# SoC.net
KiCad netlist of a schematic drawn in Altium Designer
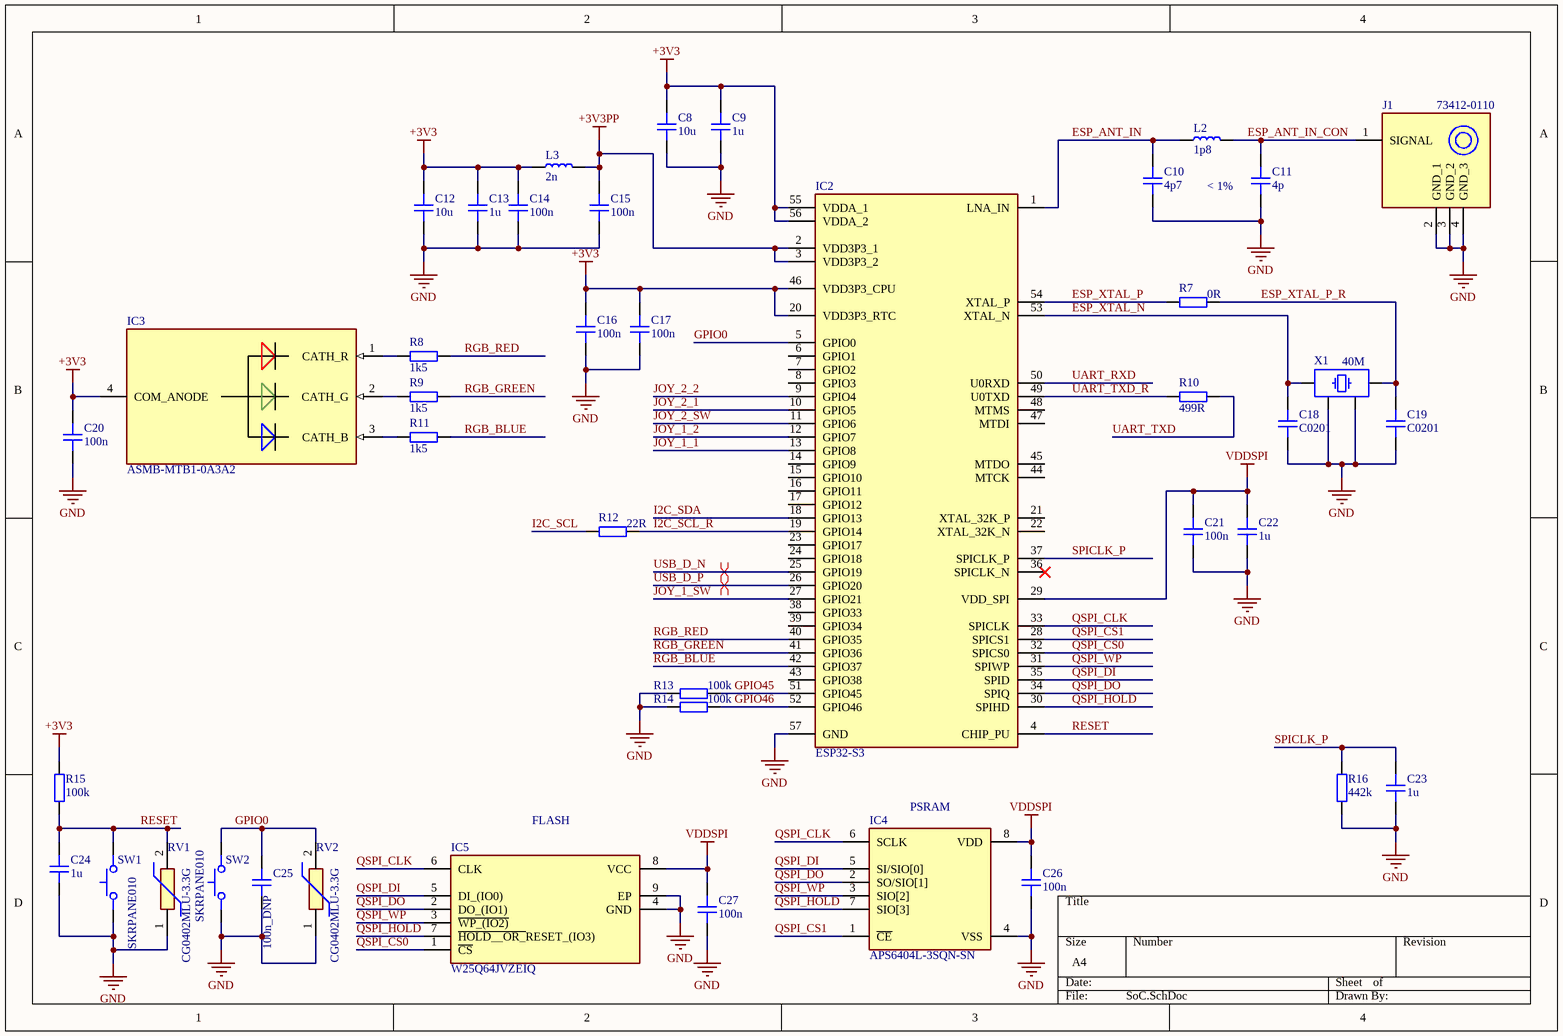
[diagram p0: SoC.SchDoc]

(export (version "E")
  (design (tool "Eeschema 10.0.6"))
  (components
    (comp (ref "C8")
      (value "10u")
      (footprint "CAP_0402")
      (description "Capacitor SMD 0402")
      (libsource (lib "Schematic-Lib-PhilsLab") (part "CAP_0402"))
    )
    (comp (ref "C9")
      (value "1u")
      (footprint "CAP_0201")
      (description "Capacitor SMD 0201")
      (libsource (lib "Schematic-Lib-PhilsLab") (part "CAP_0201"))
    )
    (comp (ref "C10")
      (value "4p7")
      (footprint "CAP_0201")
      (description "Capacitor SMD 0201")
      (libsource (lib "Schematic-Lib-PhilsLab") (part "CAP_0201"))
    )
    (comp (ref "C11")
      (value "4p")
      (footprint "CAP_0201")
      (description "Capacitor SMD 0201")
      (libsource (lib "Schematic-Lib-PhilsLab") (part "CAP_0201"))
    )
    (comp (ref "C12")
      (value "10u")
      (footprint "CAP_0402")
      (description "Capacitor SMD 0402")
      (libsource (lib "Schematic-Lib-PhilsLab") (part "CAP_0402"))
    )
    (comp (ref "C13")
      (value "1u")
      (footprint "CAP_0201")
      (description "Capacitor SMD 0201")
      (libsource (lib "Schematic-Lib-PhilsLab") (part "CAP_0201"))
    )
    (comp (ref "C14")
      (value "100n")
      (footprint "CAP_0201")
      (description "Capacitor SMD 0201")
      (libsource (lib "Schematic-Lib-PhilsLab") (part "CAP_0201"))
    )
    (comp (ref "C15")
      (value "100n")
      (footprint "CAP_0201")
      (description "Capacitor SMD 0201")
      (libsource (lib "Schematic-Lib-PhilsLab") (part "CAP_0201"))
    )
    (comp (ref "C16")
      (value "100n")
      (footprint "CAP_0201")
      (description "Capacitor SMD 0201")
      (libsource (lib "Schematic-Lib-PhilsLab") (part "CAP_0201"))
    )
    (comp (ref "C17")
      (value "100n")
      (footprint "CAP_0201")
      (description "Capacitor SMD 0201")
      (libsource (lib "Schematic-Lib-PhilsLab") (part "CAP_0201"))
    )
    (comp (ref "C18")
      (value "C0201")
      (footprint "CAP_0201")
      (description "Capacitor SMD 0201")
      (libsource (lib "Schematic-Lib-PhilsLab") (part "CAP_0201"))
    )
    (comp (ref "C19")
      (value "C0201")
      (footprint "CAP_0201")
      (description "Capacitor SMD 0201")
      (libsource (lib "Schematic-Lib-PhilsLab") (part "CAP_0201"))
    )
    (comp (ref "C20")
      (value "100n")
      (footprint "CAP_0201")
      (description "Capacitor SMD 0201")
      (libsource (lib "Schematic-Lib-PhilsLab") (part "CAP_0201"))
    )
    (comp (ref "C21")
      (value "100n")
      (footprint "CAP_0201")
      (description "Capacitor SMD 0201")
      (libsource (lib "Schematic-Lib-PhilsLab") (part "CAP_0201"))
    )
    (comp (ref "C22")
      (value "1u")
      (footprint "CAP_0201")
      (description "Capacitor SMD 0201")
      (libsource (lib "Schematic-Lib-PhilsLab") (part "CAP_0201"))
    )
    (comp (ref "C23")
      (value "1u")
      (footprint "CAP_0201")
      (description "Capacitor SMD 0201")
      (libsource (lib "Schematic-Lib-PhilsLab") (part "CAP_0201"))
    )
    (comp (ref "C24")
      (value "1u")
      (footprint "CAP_0201")
      (description "Capacitor SMD 0201")
      (libsource (lib "Schematic-Lib-PhilsLab") (part "CAP_0201"))
    )
    (comp (ref "C25")
      (value "100n_DNP")
      (footprint "CAP_0201")
      (description "Capacitor SMD 0201")
      (libsource (lib "Schematic-Lib-PhilsLab") (part "CAP_0201"))
    )
    (comp (ref "C26")
      (value "100n")
      (footprint "CAP_0201")
      (description "Capacitor SMD 0201")
      (libsource (lib "Schematic-Lib-PhilsLab") (part "CAP_0201"))
    )
    (comp (ref "C27")
      (value "100n")
      (footprint "CAP_0201")
      (description "Capacitor SMD 0201")
      (libsource (lib "Schematic-Lib-PhilsLab") (part "CAP_0201"))
    )
    (comp (ref "IC2")
      (value "ESP32-S3")
      (footprint "Footprint-Lib-PhilsLab:ESP32QFN40P700X700X90-57N-D")
      (description "Integrated Circuit")
      (fields (field (name "MOUSER PART NUMBER") "356-ESP32-S3"))
      (libsource (lib "Schematic-Lib-PhilsLab") (part "ESP32-S3"))
    )
    (comp (ref "IC3")
      (value "ASMB-MTB1-0A3A2")
      (footprint "BAT_Detector_PCBLib:AVAGO_PLCC4")
      (description "Integrated Circuit")
      (fields (field (name "MOUSER PART NUMBER") "630-ASMB-MTB1-0A3A2"))
      (libsource (lib "Schematic-Lib-PhilsLab") (part "ASMB-MTB1-0A3A2"))
    )
    (comp (ref "IC4")
      (value "APS6404L-3SQN-SN")
      (footprint "Footprint-Lib-PhilsLab:SOIC127P600X175-8N - duplicate")
      (description "Integrated Circuit")
      (fields (field (name "MOUSER PART NUMBER") "878-APS6404L-3SQN-SN"))
      (libsource (lib "Schematic-Lib-PhilsLab") (part "APS6404L-3SQN-SN"))
    )
    (comp (ref "IC5")
      (value "W25Q64JVZEIQ")
      (footprint "Footprint-Lib-PhilsLab:SON127P800X600X80-9N-D")
      (description "Integrated Circuit")
      (fields (field (name "MOUSER PART NUMBER") "454-W25Q64JVZEIQ"))
      (libsource (lib "Schematic-Lib-PhilsLab") (part "W25Q64JVZEIQ"))
    )
    (comp (ref "J1")
      (value "73412-0110")
      (footprint "Footprint-Lib-PhilsLab:73412-0110")
      (description "Connector")
      (fields (field (name "MOUSER PART NUMBER") "538-73412-0110"))
      (libsource (lib "Schematic-Lib-PhilsLab") (part "73412-0110"))
    )
    (comp (ref "L2")
      (value "1p8")
      (footprint "Footprint-Lib-PhilsLab:IND_0201")
      (description "Inductor SMD 0201")
      (fields
        (field (name "MANUFACTURER_PART_NUMBER") "LQP03HQ56NH02D")
        (field (name "MOUSER PART NUMBER") "81-LQP03HQ56NH02D")
      )
      (libsource (lib "Schematic-Lib-PhilsLab") (part "IND_0201"))
    )
    (comp (ref "L3")
      (value "2n")
      (footprint "Footprint-Lib-PhilsLab:IND_0201")
      (description "Inductor SMD 0201")
      (fields
        (field (name "MANUFACTURER_PART_NUMBER") "LQP03HQ56NH02D")
        (field (name "MOUSER PART NUMBER") "81-LQP03HQ56NH02D")
      )
      (libsource (lib "Schematic-Lib-PhilsLab") (part "IND_0201"))
    )
    (comp (ref "R7")
      (value "0R")
      (footprint "RES_0201")
      (description "Resistor SMD 0201")
      (libsource (lib "Schematic-Lib-PhilsLab") (part "RES_0201"))
    )
    (comp (ref "R8")
      (value "1k5")
      (footprint "RES_0402")
      (description "Resistor SMD 0402")
      (libsource (lib "Schematic-Lib-PhilsLab") (part "RES_0402"))
    )
    (comp (ref "R9")
      (value "1k5")
      (footprint "RES_0402")
      (description "Resistor SMD 0402")
      (libsource (lib "Schematic-Lib-PhilsLab") (part "RES_0402"))
    )
    (comp (ref "R10")
      (value "499R")
      (footprint "RES_0201")
      (description "Resistor SMD 0201")
      (libsource (lib "Schematic-Lib-PhilsLab") (part "RES_0201"))
    )
    (comp (ref "R11")
      (value "1k5")
      (footprint "RES_0402")
      (description "Resistor SMD 0402")
      (libsource (lib "Schematic-Lib-PhilsLab") (part "RES_0402"))
    )
    (comp (ref "R12")
      (value "22R")
      (footprint "RES_0201")
      (description "Resistor SMD 0201")
      (libsource (lib "Schematic-Lib-PhilsLab") (part "RES_0201"))
    )
    (comp (ref "R13")
      (value "100k")
      (footprint "RES_0201")
      (description "Resistor SMD 0201")
      (libsource (lib "Schematic-Lib-PhilsLab") (part "RES_0201"))
    )
    (comp (ref "R14")
      (value "100k")
      (footprint "RES_0201")
      (description "Resistor SMD 0201")
      (libsource (lib "Schematic-Lib-PhilsLab") (part "RES_0201"))
    )
    (comp (ref "R15")
      (value "100k")
      (footprint "RES_0201")
      (description "Resistor SMD 0201")
      (libsource (lib "Schematic-Lib-PhilsLab") (part "RES_0201"))
    )
    (comp (ref "R16")
      (value "442k")
      (footprint "RES_0201")
      (description "Resistor SMD 0201")
      (libsource (lib "Schematic-Lib-PhilsLab") (part "RES_0201"))
    )
    (comp (ref "RV1")
      (value "CG0402MLU-3.3G")
      (footprint "Footprint-Lib-PhilsLab:VARC1005X41N")
      (description "ESD Diode")
      (fields (field (name "MOUSER PART NUMBER") "652-CG0402MLU-3.3G"))
      (libsource (lib "Schematic-Lib-PhilsLab") (part "CG0402MLU-3.3G"))
    )
    (comp (ref "RV2")
      (value "CG0402MLU-3.3G")
      (footprint "Footprint-Lib-PhilsLab:VARC1005X41N")
      (description "ESD Diode")
      (fields (field (name "MOUSER PART NUMBER") "652-CG0402MLU-3.3G"))
      (libsource (lib "Schematic-Lib-PhilsLab") (part "CG0402MLU-3.3G"))
    )
    (comp (ref "SW1")
      (value "SKRPANE010")
      (footprint "SKRPANE010")
      (description "Tactile Switch SMD SPST")
      (fields (field (name "MANUFACTURER") "Alps Alpine"))
      (libsource (lib "Schematic-Lib-PhilsLab") (part "SKRPANE010"))
    )
    (comp (ref "SW2")
      (value "SKRPANE010")
      (footprint "SKRPANE010")
      (description "Tactile Switch SMD SPST")
      (fields (field (name "MANUFACTURER") "Alps Alpine"))
      (libsource (lib "Schematic-Lib-PhilsLab") (part "SKRPANE010"))
    )
    (comp (ref "X1")
      (value "40M")
      (footprint "XTAL_2016")
      (description "Crystal SMD 4-Pin 2.0x1.6mm")
      (libsource (lib "Schematic-Lib-PhilsLab") (part "XTAL_2016"))
    )
  )
  (nets
    (net (code "1") (name "+3V3") (class "Default")
      (node (ref "C12") (pin "2") (pinfunction "2_2") (pintype "passive"))
      (node (ref "C13") (pin "2") (pinfunction "2_2") (pintype "passive"))
      (node (ref "C14") (pin "2") (pinfunction "2_2") (pintype "passive"))
      (node (ref "C16") (pin "2") (pinfunction "2_2") (pintype "passive"))
      (node (ref "C17") (pin "2") (pinfunction "2_2") (pintype "passive"))
      (node (ref "C20") (pin "2") (pinfunction "2_2") (pintype "passive"))
      (node (ref "C8") (pin "2") (pinfunction "2_2") (pintype "passive"))
      (node (ref "C9") (pin "2") (pinfunction "2_2") (pintype "passive"))
      (node (ref "IC2") (pin "20") (pinfunction "VDD3P3_RTC_20") (pintype "passive"))
      (node (ref "IC2") (pin "46") (pinfunction "VDD3P3_CPU_46") (pintype "passive"))
      (node (ref "IC2") (pin "55") (pinfunction "VDDA_1_55") (pintype "passive"))
      (node (ref "IC2") (pin "56") (pinfunction "VDDA_2_56") (pintype "passive"))
      (node (ref "IC3") (pin "4") (pinfunction "COM_ANODE_4") (pintype "power_in"))
      (node (ref "L3") (pin "1") (pinfunction "1_1") (pintype "passive"))
      (node (ref "R15") (pin "2") (pinfunction "2_2") (pintype "passive"))
    )
    (net (code "2") (name "+3V3PP") (class "Default")
      (node (ref "C15") (pin "2") (pinfunction "2_2") (pintype "passive"))
      (node (ref "IC2") (pin "2") (pinfunction "VDD3P3_1_2") (pintype "passive"))
      (node (ref "IC2") (pin "3") (pinfunction "VDD3P3_2_3") (pintype "passive"))
      (node (ref "L3") (pin "2") (pinfunction "2_2") (pintype "passive"))
    )
    (net (code "3") (name "/ESP_ANT_IN") (class "Default")
      (node (ref "C10") (pin "2") (pinfunction "2_2") (pintype "passive"))
      (node (ref "IC2") (pin "1") (pinfunction "LNA_IN_1") (pintype "passive"))
      (node (ref "L2") (pin "1") (pinfunction "1_1") (pintype "passive"))
    )
    (net (code "4") (name "/ESP_ANT_IN_CON") (class "Default")
      (node (ref "C11") (pin "2") (pinfunction "2_2") (pintype "passive"))
      (node (ref "J1") (pin "1") (pinfunction "SIGNAL_1") (pintype "passive"))
      (node (ref "L2") (pin "2") (pinfunction "2_2") (pintype "passive"))
    )
    (net (code "5") (name "/ESP_XTAL_N") (class "Default")
      (node (ref "C18") (pin "2") (pinfunction "2_2") (pintype "passive"))
      (node (ref "IC2") (pin "53") (pinfunction "XTAL_N_53") (pintype "passive"))
      (node (ref "X1") (pin "1") (pinfunction "1_1") (pintype "passive"))
    )
    (net (code "6") (name "/ESP_XTAL_P") (class "Default")
      (node (ref "IC2") (pin "54") (pinfunction "XTAL_P_54") (pintype "passive"))
      (node (ref "R7") (pin "2") (pinfunction "2_2") (pintype "passive"))
    )
    (net (code "7") (name "/ESP_XTAL_P_R") (class "Default")
      (node (ref "C19") (pin "2") (pinfunction "2_2") (pintype "passive"))
      (node (ref "R7") (pin "1") (pinfunction "1_1") (pintype "passive"))
      (node (ref "X1") (pin "3") (pinfunction "3_3") (pintype "passive"))
    )
    (net (code "8") (name "/GPIO0") (class "Default")
      (node (ref "C25") (pin "2") (pinfunction "2_2") (pintype "passive"))
      (node (ref "IC2") (pin "5") (pinfunction "GPIO0_5") (pintype "passive"))
      (node (ref "RV2") (pin "2") (pinfunction "2_2") (pintype "passive"))
      (node (ref "SW2") (pin "34") (pintype "passive"))
    )
    (net (code "9") (name "/GPIO45") (class "Default")
      (node (ref "IC2") (pin "51") (pinfunction "GPIO45_51") (pintype "passive"))
      (node (ref "R13") (pin "1") (pinfunction "1_1") (pintype "passive"))
    )
    (net (code "10") (name "/GPIO46") (class "Default")
      (node (ref "IC2") (pin "52") (pinfunction "GPIO46_52") (pintype "passive"))
      (node (ref "R14") (pin "1") (pinfunction "1_1") (pintype "passive"))
    )
    (net (code "11") (name "/I2C_SCL") (class "Default")
      (node (ref "R12") (pin "2") (pinfunction "2_2") (pintype "passive"))
    )
    (net (code "12") (name "/I2C_SCL_R") (class "Default")
      (node (ref "IC2") (pin "19") (pinfunction "GPIO14_19") (pintype "passive"))
      (node (ref "R12") (pin "1") (pinfunction "1_1") (pintype "passive"))
    )
    (net (code "13") (name "/I2C_SDA") (class "Default")
      (node (ref "IC2") (pin "18") (pinfunction "GPIO13_18") (pintype "passive"))
    )
    (net (code "14") (name "/JOY_1_1") (class "Default")
      (node (ref "IC2") (pin "13") (pinfunction "GPIO8_13") (pintype "passive"))
    )
    (net (code "15") (name "/JOY_1_2") (class "Default")
      (node (ref "IC2") (pin "12") (pinfunction "GPIO7_12") (pintype "passive"))
    )
    (net (code "16") (name "/JOY_1_SW") (class "Default")
      (node (ref "IC2") (pin "27") (pinfunction "GPIO21_27") (pintype "passive"))
    )
    (net (code "17") (name "/JOY_2_1") (class "Default")
      (node (ref "IC2") (pin "10") (pinfunction "GPIO5_10") (pintype "passive"))
    )
    (net (code "18") (name "/JOY_2_2") (class "Default")
      (node (ref "IC2") (pin "9") (pinfunction "GPIO4_9") (pintype "passive"))
    )
    (net (code "19") (name "/JOY_2_SW") (class "Default")
      (node (ref "IC2") (pin "11") (pinfunction "GPIO6_11") (pintype "passive"))
    )
    (net (code "20") (name "/QSPI_CLK") (class "Default")
      (node (ref "IC2") (pin "33") (pinfunction "SPICLK_33") (pintype "passive"))
      (node (ref "IC4") (pin "6") (pinfunction "SCLK_6") (pintype "passive"))
      (node (ref "IC5") (pin "6") (pinfunction "CLK_6") (pintype "passive"))
    )
    (net (code "21") (name "/QSPI_CS0") (class "Default")
      (node (ref "IC2") (pin "32") (pinfunction "SPICS0_32") (pintype "passive"))
      (node (ref "IC5") (pin "1") (pinfunction "~{CS}_1") (pintype "passive"))
    )
    (net (code "22") (name "/QSPI_CS1") (class "Default")
      (node (ref "IC2") (pin "28") (pinfunction "SPICS1_28") (pintype "passive"))
      (node (ref "IC4") (pin "1") (pinfunction "~{CE}_1") (pintype "passive"))
    )
    (net (code "23") (name "/QSPI_DI") (class "Default")
      (node (ref "IC2") (pin "35") (pinfunction "SPID_35") (pintype "passive"))
      (node (ref "IC4") (pin "5") (pinfunction "SI/SIO[0]_5") (pintype "passive"))
      (node (ref "IC5") (pin "5") (pinfunction "DI_(IO0)_5") (pintype "passive"))
    )
    (net (code "24") (name "/QSPI_DO") (class "Default")
      (node (ref "IC2") (pin "34") (pinfunction "SPIQ_34") (pintype "passive"))
      (node (ref "IC4") (pin "2") (pinfunction "SO/SIO[1]_2") (pintype "passive"))
      (node (ref "IC5") (pin "2") (pinfunction "DO_(IO1)_2") (pintype "passive"))
    )
    (net (code "25") (name "/QSPI_HOLD") (class "Default")
      (node (ref "IC2") (pin "30") (pinfunction "SPIHD_30") (pintype "passive"))
      (node (ref "IC4") (pin "7") (pinfunction "SIO[3]_7") (pintype "passive"))
      (node (ref "IC5") (pin "7") (pinfunction "~{HOLD__OR_}RESET_(IO3)_7") (pintype "passive"))
    )
    (net (code "26") (name "/QSPI_WP") (class "Default")
      (node (ref "IC2") (pin "31") (pinfunction "SPIWP_31") (pintype "passive"))
      (node (ref "IC4") (pin "3") (pinfunction "SIO[2]_3") (pintype "passive"))
      (node (ref "IC5") (pin "3") (pinfunction "~{WP_(IO2)}_3") (pintype "passive"))
    )
    (net (code "27") (name "/RESET") (class "Default")
      (node (ref "C24") (pin "2") (pinfunction "2_2") (pintype "passive"))
      (node (ref "IC2") (pin "4") (pinfunction "CHIP_PU_4") (pintype "passive"))
      (node (ref "R15") (pin "1") (pinfunction "1_1") (pintype "passive"))
      (node (ref "RV1") (pin "2") (pinfunction "2_2") (pintype "passive"))
      (node (ref "SW1") (pin "34") (pintype "passive"))
    )
    (net (code "28") (name "/RGB_BLUE") (class "Default")
      (node (ref "IC2") (pin "42") (pinfunction "GPIO37_42") (pintype "passive"))
      (node (ref "R11") (pin "2") (pinfunction "2_2") (pintype "passive"))
    )
    (net (code "29") (name "/RGB_GREEN") (class "Default")
      (node (ref "IC2") (pin "41") (pinfunction "GPIO36_41") (pintype "passive"))
      (node (ref "R9") (pin "2") (pinfunction "2_2") (pintype "passive"))
    )
    (net (code "30") (name "/RGB_RED") (class "Default")
      (node (ref "IC2") (pin "40") (pinfunction "GPIO35_40") (pintype "passive"))
      (node (ref "R8") (pin "2") (pinfunction "2_2") (pintype "passive"))
    )
    (net (code "31") (name "/SPICLK_P") (class "Default")
      (node (ref "C23") (pin "2") (pinfunction "2_2") (pintype "passive"))
      (node (ref "IC2") (pin "37") (pinfunction "SPICLK_P_37") (pintype "passive"))
      (node (ref "R16") (pin "2") (pinfunction "2_2") (pintype "passive"))
    )
    (net (code "32") (name "/UART_RXD") (class "Default")
      (node (ref "IC2") (pin "50") (pinfunction "U0RXD_50") (pintype "passive"))
    )
    (net (code "33") (name "/UART_TXD") (class "Default")
      (node (ref "R10") (pin "1") (pinfunction "1_1") (pintype "passive"))
    )
    (net (code "34") (name "/UART_TXD_R") (class "Default")
      (node (ref "IC2") (pin "49") (pinfunction "U0TXD_49") (pintype "passive"))
      (node (ref "R10") (pin "2") (pinfunction "2_2") (pintype "passive"))
    )
    (net (code "35") (name "/USB_D_N") (class "Default")
      (node (ref "IC2") (pin "25") (pinfunction "GPIO19_25") (pintype "passive"))
    )
    (net (code "36") (name "/USB_D_P") (class "Default")
      (node (ref "IC2") (pin "26") (pinfunction "GPIO20_26") (pintype "passive"))
    )
    (net (code "37") (name "GND") (class "Default")
      (node (ref "C10") (pin "1") (pinfunction "1_1") (pintype "passive"))
      (node (ref "C11") (pin "1") (pinfunction "1_1") (pintype "passive"))
      (node (ref "C12") (pin "1") (pinfunction "1_1") (pintype "passive"))
      (node (ref "C13") (pin "1") (pinfunction "1_1") (pintype "passive"))
      (node (ref "C14") (pin "1") (pinfunction "1_1") (pintype "passive"))
      (node (ref "C15") (pin "1") (pinfunction "1_1") (pintype "passive"))
      (node (ref "C16") (pin "1") (pinfunction "1_1") (pintype "passive"))
      (node (ref "C17") (pin "1") (pinfunction "1_1") (pintype "passive"))
      (node (ref "C18") (pin "1") (pinfunction "1_1") (pintype "passive"))
      (node (ref "C19") (pin "1") (pinfunction "1_1") (pintype "passive"))
      (node (ref "C20") (pin "1") (pinfunction "1_1") (pintype "passive"))
      (node (ref "C21") (pin "1") (pinfunction "1_1") (pintype "passive"))
      (node (ref "C22") (pin "1") (pinfunction "1_1") (pintype "passive"))
      (node (ref "C23") (pin "1") (pinfunction "1_1") (pintype "passive"))
      (node (ref "C24") (pin "1") (pinfunction "1_1") (pintype "passive"))
      (node (ref "C25") (pin "1") (pinfunction "1_1") (pintype "passive"))
      (node (ref "C26") (pin "1") (pinfunction "1_1") (pintype "passive"))
      (node (ref "C27") (pin "1") (pinfunction "1_1") (pintype "passive"))
      (node (ref "C8") (pin "1") (pinfunction "1_1") (pintype "passive"))
      (node (ref "C9") (pin "1") (pinfunction "1_1") (pintype "passive"))
      (node (ref "IC2") (pin "57") (pinfunction "GND_57") (pintype "passive"))
      (node (ref "IC4") (pin "4") (pinfunction "VSS_4") (pintype "passive"))
      (node (ref "IC5") (pin "4") (pinfunction "GND_4") (pintype "passive"))
      (node (ref "IC5") (pin "9") (pinfunction "EP_9") (pintype "passive"))
      (node (ref "J1") (pin "2") (pinfunction "GND_1_2") (pintype "passive"))
      (node (ref "J1") (pin "3") (pinfunction "GND_2_3") (pintype "passive"))
      (node (ref "J1") (pin "4") (pinfunction "GND_3_4") (pintype "passive"))
      (node (ref "R13") (pin "2") (pinfunction "2_2") (pintype "passive"))
      (node (ref "R14") (pin "2") (pinfunction "2_2") (pintype "passive"))
      (node (ref "R16") (pin "1") (pinfunction "1_1") (pintype "passive"))
      (node (ref "RV1") (pin "1") (pinfunction "1_1") (pintype "passive"))
      (node (ref "RV2") (pin "1") (pinfunction "1_1") (pintype "passive"))
      (node (ref "SW1") (pin "12") (pintype "passive"))
      (node (ref "SW2") (pin "12") (pintype "passive"))
      (node (ref "X1") (pin "2") (pinfunction "2_2") (pintype "passive"))
      (node (ref "X1") (pin "4") (pinfunction "4_4") (pintype "passive"))
    )
    (net (code "38") (name "Net-(IC3-CATH_B)") (class "Default")
      (node (ref "IC3") (pin "3") (pinfunction "CATH_B_3") (pintype "input"))
      (node (ref "R11") (pin "1") (pinfunction "1_1") (pintype "passive"))
    )
    (net (code "39") (name "Net-(IC3-CATH_G)") (class "Default")
      (node (ref "IC3") (pin "2") (pinfunction "CATH_G_2") (pintype "input"))
      (node (ref "R9") (pin "1") (pinfunction "1_1") (pintype "passive"))
    )
    (net (code "40") (name "Net-(IC3-CATH_R)") (class "Default")
      (node (ref "IC3") (pin "1") (pinfunction "CATH_R_1") (pintype "input"))
      (node (ref "R8") (pin "1") (pinfunction "1_1") (pintype "passive"))
    )
    (net (code "41") (name "VDDSPI") (class "Default")
      (node (ref "C21") (pin "2") (pinfunction "2_2") (pintype "passive"))
      (node (ref "C22") (pin "2") (pinfunction "2_2") (pintype "passive"))
      (node (ref "C26") (pin "2") (pinfunction "2_2") (pintype "passive"))
      (node (ref "C27") (pin "2") (pinfunction "2_2") (pintype "passive"))
      (node (ref "IC2") (pin "29") (pinfunction "VDD_SPI_29") (pintype "passive"))
      (node (ref "IC4") (pin "8") (pinfunction "VDD_8") (pintype "passive"))
      (node (ref "IC5") (pin "8") (pinfunction "VCC_8") (pintype "passive"))
    )
    (net (code "42") (name "unconnected-(IC2-GPIO1-Pad6)") (class "Default")
      (node (ref "IC2") (pin "6") (pinfunction "GPIO1_6") (pintype "passive"))
    )
    (net (code "43") (name "unconnected-(IC2-GPIO2-Pad7)") (class "Default")
      (node (ref "IC2") (pin "7") (pinfunction "GPIO2_7") (pintype "passive"))
    )
    (net (code "44") (name "unconnected-(IC2-GPIO3-Pad8)") (class "Default")
      (node (ref "IC2") (pin "8") (pinfunction "GPIO3_8") (pintype "passive"))
    )
    (net (code "45") (name "unconnected-(IC2-GPIO9-Pad14)") (class "Default")
      (node (ref "IC2") (pin "14") (pinfunction "GPIO9_14") (pintype "passive"))
    )
    (net (code "46") (name "unconnected-(IC2-GPIO10-Pad15)") (class "Default")
      (node (ref "IC2") (pin "15") (pinfunction "GPIO10_15") (pintype "passive"))
    )
    (net (code "47") (name "unconnected-(IC2-GPIO11-Pad16)") (class "Default")
      (node (ref "IC2") (pin "16") (pinfunction "GPIO11_16") (pintype "passive"))
    )
    (net (code "48") (name "unconnected-(IC2-GPIO12-Pad17)") (class "Default")
      (node (ref "IC2") (pin "17") (pinfunction "GPIO12_17") (pintype "passive"))
    )
    (net (code "49") (name "unconnected-(IC2-GPIO17-Pad23)") (class "Default")
      (node (ref "IC2") (pin "23") (pinfunction "GPIO17_23") (pintype "passive"))
    )
    (net (code "50") (name "unconnected-(IC2-GPIO18-Pad24)") (class "Default")
      (node (ref "IC2") (pin "24") (pinfunction "GPIO18_24") (pintype "passive"))
    )
    (net (code "51") (name "unconnected-(IC2-GPIO33-Pad38)") (class "Default")
      (node (ref "IC2") (pin "38") (pinfunction "GPIO33_38") (pintype "passive"))
    )
    (net (code "52") (name "unconnected-(IC2-GPIO34-Pad39)") (class "Default")
      (node (ref "IC2") (pin "39") (pinfunction "GPIO34_39") (pintype "passive"))
    )
    (net (code "53") (name "unconnected-(IC2-GPIO38-Pad43)") (class "Default")
      (node (ref "IC2") (pin "43") (pinfunction "GPIO38_43") (pintype "passive"))
    )
    (net (code "54") (name "unconnected-(IC2-MTCK-Pad44)") (class "Default")
      (node (ref "IC2") (pin "44") (pinfunction "MTCK_44") (pintype "passive"))
    )
    (net (code "55") (name "unconnected-(IC2-MTDI-Pad47)") (class "Default")
      (node (ref "IC2") (pin "47") (pinfunction "MTDI_47") (pintype "passive"))
    )
    (net (code "56") (name "unconnected-(IC2-MTDO-Pad45)") (class "Default")
      (node (ref "IC2") (pin "45") (pinfunction "MTDO_45") (pintype "passive"))
    )
    (net (code "57") (name "unconnected-(IC2-MTMS-Pad48)") (class "Default")
      (node (ref "IC2") (pin "48") (pinfunction "MTMS_48") (pintype "passive"))
    )
    (net (code "58") (name "unconnected-(IC2-SPICLK_N-Pad36)") (class "Default")
      (node (ref "IC2") (pin "36") (pinfunction "SPICLK_N_36") (pintype "passive+no_connect"))
    )
    (net (code "59") (name "unconnected-(IC2-XTAL_32K_N-Pad22)") (class "Default")
      (node (ref "IC2") (pin "22") (pinfunction "XTAL_32K_N_22") (pintype "passive"))
    )
    (net (code "60") (name "unconnected-(IC2-XTAL_32K_P-Pad21)") (class "Default")
      (node (ref "IC2") (pin "21") (pinfunction "XTAL_32K_P_21") (pintype "passive"))
    )
  )
)
